# Buttons_SCHEMATIC.net
KiCad netlist of a schematic drawn in Altium Designer
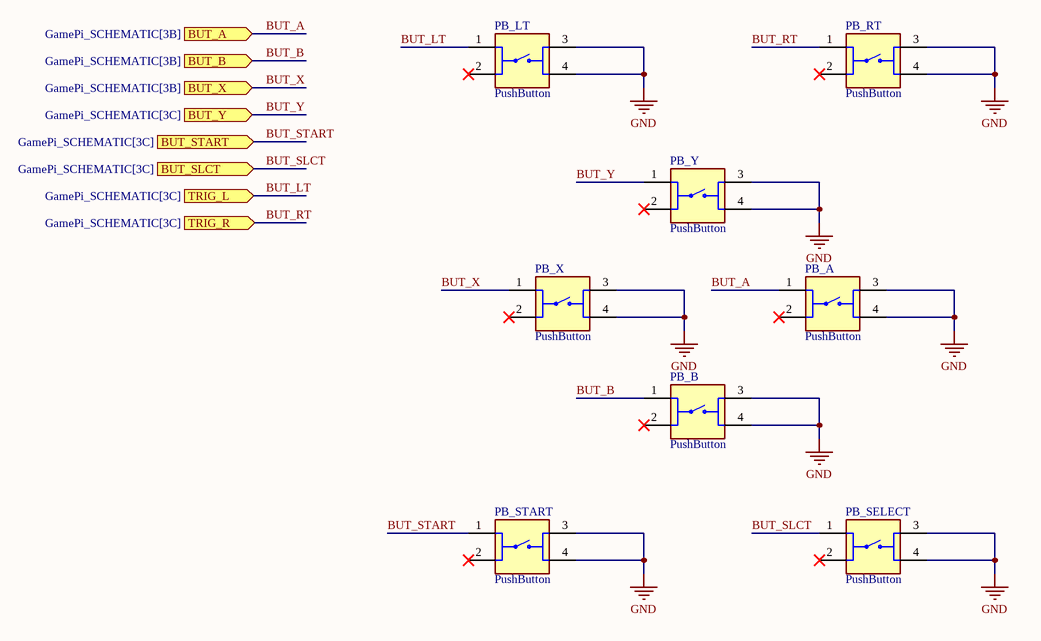
[diagram p0: Buttons_SCHEMATIC.SchDoc]

(export (version "E")
  (design (tool "Eeschema 10.0.6"))
  (components
    (comp (ref "PB_A")
      (value "PushButton")
      (footprint "Push Button")
      (libsource (lib "GamePi SCH LIB") (part "PushButton"))
    )
    (comp (ref "PB_B")
      (value "PushButton")
      (footprint "Push Button")
      (libsource (lib "GamePi SCH LIB") (part "PushButton"))
    )
    (comp (ref "PB_LT")
      (value "PushButton")
      (footprint "Push Button")
      (libsource (lib "GamePi SCH LIB") (part "PushButton"))
    )
    (comp (ref "PB_RT")
      (value "PushButton")
      (footprint "Push Button")
      (libsource (lib "GamePi SCH LIB") (part "PushButton"))
    )
    (comp (ref "PB_SELECT")
      (value "PushButton")
      (footprint "Push Button")
      (libsource (lib "GamePi SCH LIB") (part "PushButton"))
    )
    (comp (ref "PB_START")
      (value "PushButton")
      (footprint "Push Button")
      (libsource (lib "GamePi SCH LIB") (part "PushButton"))
    )
    (comp (ref "PB_X")
      (value "PushButton")
      (footprint "Push Button")
      (libsource (lib "GamePi SCH LIB") (part "PushButton"))
    )
    (comp (ref "PB_Y")
      (value "PushButton")
      (footprint "Push Button")
      (libsource (lib "GamePi SCH LIB") (part "PushButton"))
    )
  )
  (nets
    (net (code "1") (name "/BUT_A") (class "Default")
      (node (ref "PB_A") (pin "1") (pinfunction "1_1") (pintype "passive"))
    )
    (net (code "2") (name "/BUT_B") (class "Default")
      (node (ref "PB_B") (pin "1") (pinfunction "1_1") (pintype "passive"))
    )
    (net (code "3") (name "/BUT_LT") (class "Default")
      (node (ref "PB_LT") (pin "1") (pinfunction "1_1") (pintype "passive"))
    )
    (net (code "4") (name "/BUT_RT") (class "Default")
      (node (ref "PB_RT") (pin "1") (pinfunction "1_1") (pintype "passive"))
    )
    (net (code "5") (name "/BUT_SLCT") (class "Default")
      (node (ref "PB_SELECT") (pin "1") (pinfunction "1_1") (pintype "passive"))
    )
    (net (code "6") (name "/BUT_START") (class "Default")
      (node (ref "PB_START") (pin "1") (pinfunction "1_1") (pintype "passive"))
    )
    (net (code "7") (name "/BUT_X") (class "Default")
      (node (ref "PB_X") (pin "1") (pinfunction "1_1") (pintype "passive"))
    )
    (net (code "8") (name "/BUT_Y") (class "Default")
      (node (ref "PB_Y") (pin "1") (pinfunction "1_1") (pintype "passive"))
    )
    (net (code "9") (name "GND") (class "Default")
      (node (ref "PB_A") (pin "3") (pinfunction "3_3") (pintype "passive"))
      (node (ref "PB_A") (pin "4") (pinfunction "4_4") (pintype "passive"))
      (node (ref "PB_B") (pin "3") (pinfunction "3_3") (pintype "passive"))
      (node (ref "PB_B") (pin "4") (pinfunction "4_4") (pintype "passive"))
      (node (ref "PB_LT") (pin "3") (pinfunction "3_3") (pintype "passive"))
      (node (ref "PB_LT") (pin "4") (pinfunction "4_4") (pintype "passive"))
      (node (ref "PB_RT") (pin "3") (pinfunction "3_3") (pintype "passive"))
      (node (ref "PB_RT") (pin "4") (pinfunction "4_4") (pintype "passive"))
      (node (ref "PB_SELECT") (pin "3") (pinfunction "3_3") (pintype "passive"))
      (node (ref "PB_SELECT") (pin "4") (pinfunction "4_4") (pintype "passive"))
      (node (ref "PB_START") (pin "3") (pinfunction "3_3") (pintype "passive"))
      (node (ref "PB_START") (pin "4") (pinfunction "4_4") (pintype "passive"))
      (node (ref "PB_X") (pin "3") (pinfunction "3_3") (pintype "passive"))
      (node (ref "PB_X") (pin "4") (pinfunction "4_4") (pintype "passive"))
      (node (ref "PB_Y") (pin "3") (pinfunction "3_3") (pintype "passive"))
      (node (ref "PB_Y") (pin "4") (pinfunction "4_4") (pintype "passive"))
    )
    (net (code "10") (name "unconnected-(PB_A-Pad2)") (class "Default")
      (node (ref "PB_A") (pin "2") (pinfunction "2_2") (pintype "passive+no_connect"))
    )
    (net (code "11") (name "unconnected-(PB_B-Pad2)") (class "Default")
      (node (ref "PB_B") (pin "2") (pinfunction "2_2") (pintype "passive+no_connect"))
    )
    (net (code "12") (name "unconnected-(PB_LT-Pad2)") (class "Default")
      (node (ref "PB_LT") (pin "2") (pinfunction "2_2") (pintype "passive+no_connect"))
    )
    (net (code "13") (name "unconnected-(PB_RT-Pad2)") (class "Default")
      (node (ref "PB_RT") (pin "2") (pinfunction "2_2") (pintype "passive+no_connect"))
    )
    (net (code "14") (name "unconnected-(PB_SELECT-Pad2)") (class "Default")
      (node (ref "PB_SELECT") (pin "2") (pinfunction "2_2") (pintype "passive+no_connect"))
    )
    (net (code "15") (name "unconnected-(PB_START-Pad2)") (class "Default")
      (node (ref "PB_START") (pin "2") (pinfunction "2_2") (pintype "passive+no_connect"))
    )
    (net (code "16") (name "unconnected-(PB_X-Pad2)") (class "Default")
      (node (ref "PB_X") (pin "2") (pinfunction "2_2") (pintype "passive+no_connect"))
    )
    (net (code "17") (name "unconnected-(PB_Y-Pad2)") (class "Default")
      (node (ref "PB_Y") (pin "2") (pinfunction "2_2") (pintype "passive+no_connect"))
    )
  )
)
